# puissance_alim.net
KiCad netlist of a schematic drawn in EAGLE
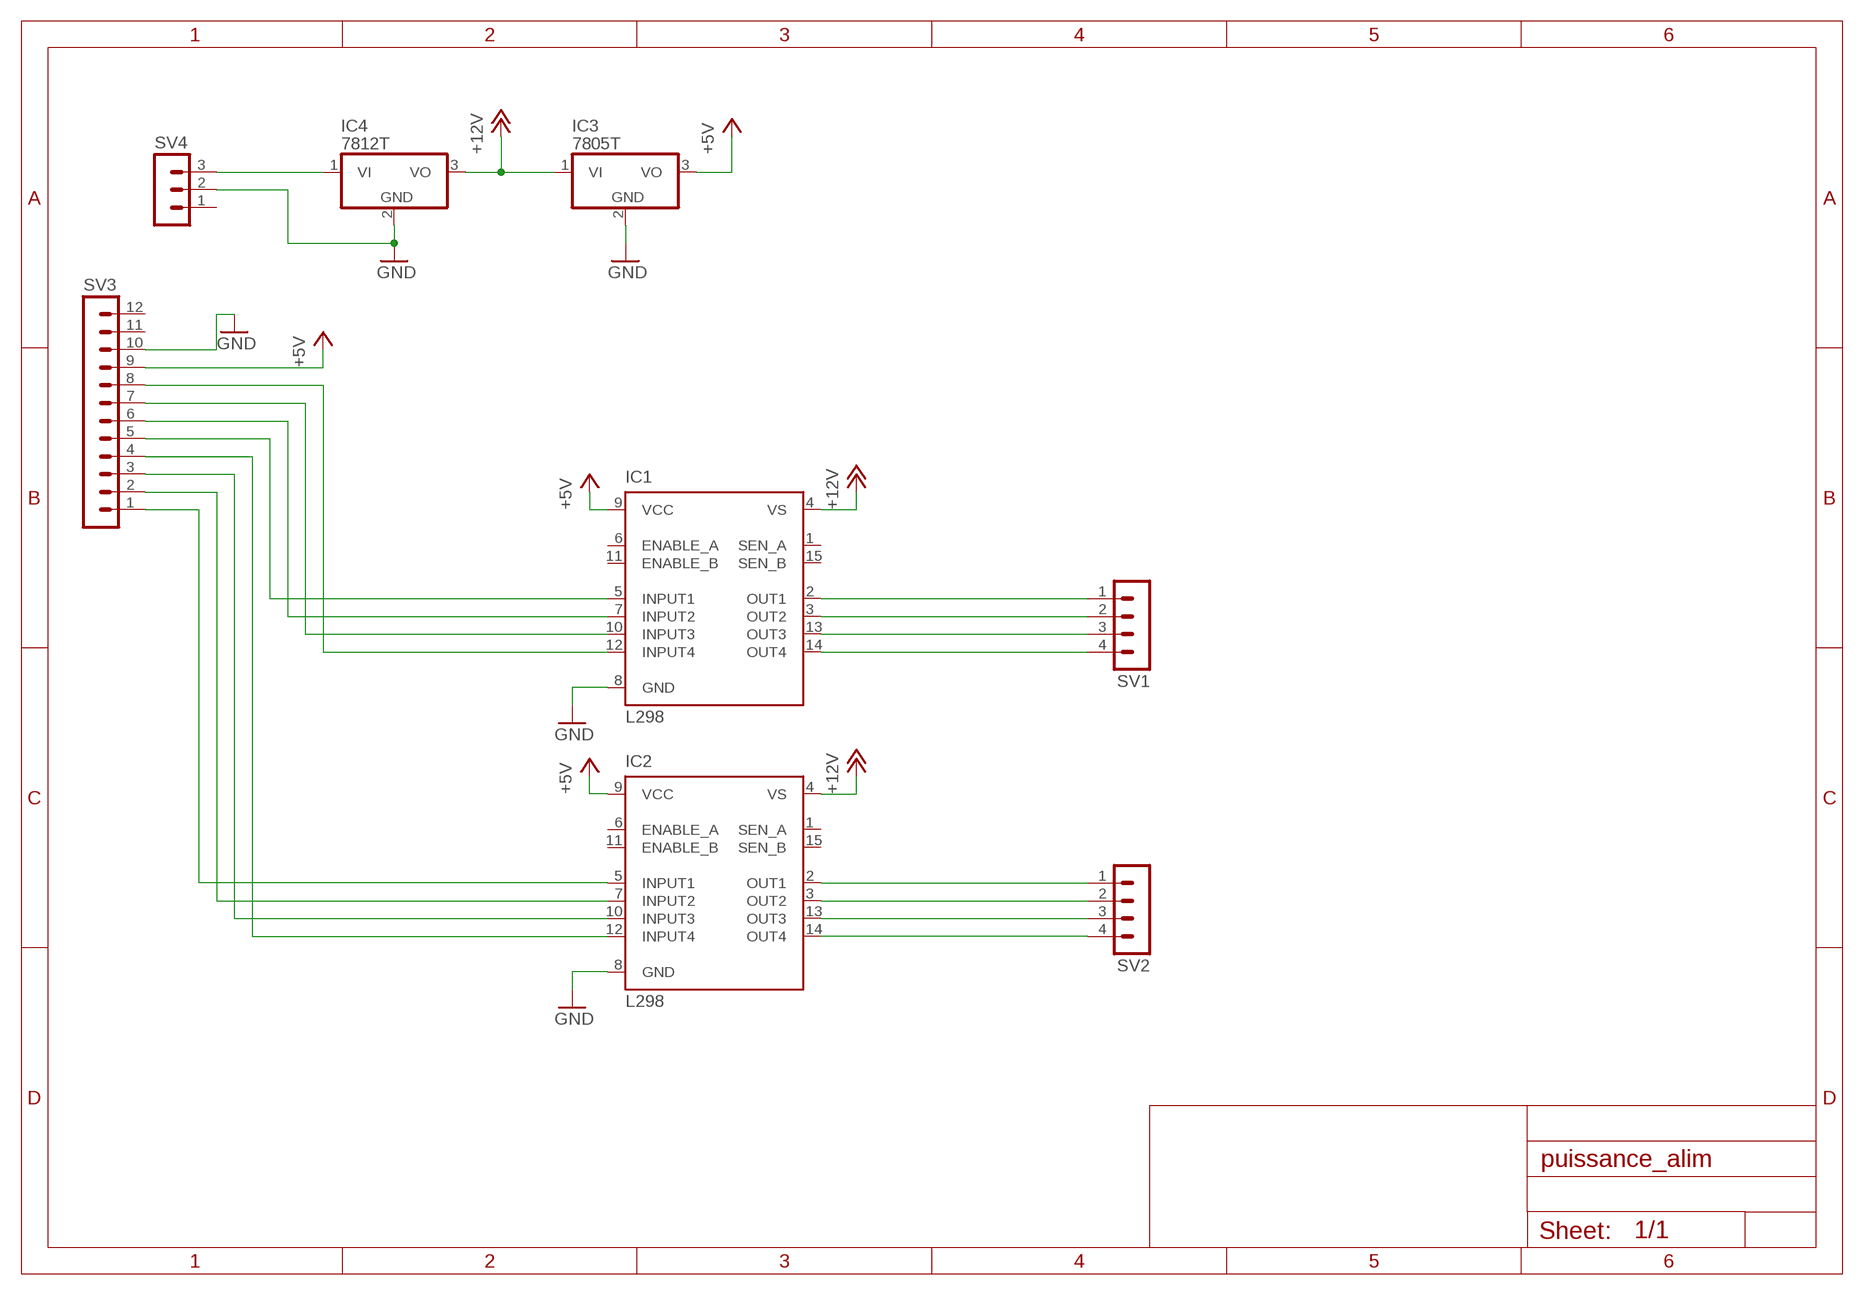
[diagram p0: schematic, sheet 1]

(export (version "E")
  (design (tool "Eeschema 10.0.6"))
  (components
    (comp (ref "IC1")
      (value "L298")
      (footprint "eagle-import:MULTIWATT-15")
      (fields (field (name "MPN") "L298N"))
      (libsource (lib "eagle-import") (part "L298"))
    )
    (comp (ref "IC2")
      (value "L298")
      (footprint "eagle-import:MULTIWATT-15")
      (fields (field (name "MPN") "L298N"))
      (libsource (lib "eagle-import") (part "L298"))
    )
    (comp (ref "IC3")
      (value "7805T")
      (footprint "eagle-import:TO220H")
      (libsource (lib "eagle-import") (part "78T05"))
    )
    (comp (ref "IC4")
      (value "7812T")
      (footprint "eagle-import:TO220H")
      (libsource (lib "eagle-import") (part "78T12"))
    )
    (comp (ref "SV1")
      (value "MA04-1")
      (footprint "eagle-import:MA04-1")
      (libsource (lib "eagle-import") (part "MA04-1"))
    )
    (comp (ref "SV2")
      (value "MA04-1")
      (footprint "eagle-import:MA04-1")
      (libsource (lib "eagle-import") (part "MA04-1"))
    )
    (comp (ref "SV3")
      (value "MA12-1")
      (footprint "eagle-import:MA12-1")
      (libsource (lib "eagle-import") (part "MA12-1"))
    )
    (comp (ref "SV4")
      (value "MA03-1")
      (footprint "eagle-import:MA03-1")
      (libsource (lib "eagle-import") (part "MA03-1"))
    )
  )
  (nets
    (net (code "1") (name "+5V") (class "Default")
      (node (ref "IC1") (pin "9") (pinfunction "VCC_9") (pintype "power_in"))
      (node (ref "IC2") (pin "9") (pinfunction "VCC_9") (pintype "power_in"))
      (node (ref "IC3") (pin "3") (pinfunction "VO_3") (pintype "passive"))
      (node (ref "SV3") (pin "9") (pinfunction "9_9") (pintype "passive"))
    )
    (net (code "2") (name "+12V") (class "Default")
      (node (ref "IC1") (pin "4") (pinfunction "VS_4") (pintype "power_in"))
      (node (ref "IC2") (pin "4") (pinfunction "VS_4") (pintype "power_in"))
      (node (ref "IC3") (pin "1") (pinfunction "VI_1") (pintype "input"))
      (node (ref "IC4") (pin "3") (pinfunction "VO_3") (pintype "passive"))
    )
    (net (code "3") (name "GND") (class "Default")
      (node (ref "IC1") (pin "8") (pinfunction "GND_8") (pintype "power_in"))
      (node (ref "IC2") (pin "8") (pinfunction "GND_8") (pintype "power_in"))
      (node (ref "IC3") (pin "2") (pinfunction "GND_2") (pintype "passive"))
      (node (ref "IC4") (pin "2") (pinfunction "GND_2") (pintype "passive"))
      (node (ref "SV3") (pin "10") (pinfunction "10_10") (pintype "passive"))
      (node (ref "SV4") (pin "2") (pinfunction "2_2") (pintype "passive"))
    )
    (net (code "4") (name "Net-(IC1-INPUT1)") (class "Default")
      (node (ref "IC1") (pin "5") (pinfunction "INPUT1_5") (pintype "input"))
      (node (ref "SV3") (pin "5") (pinfunction "5_5") (pintype "passive"))
    )
    (net (code "5") (name "Net-(IC1-INPUT2)") (class "Default")
      (node (ref "IC1") (pin "7") (pinfunction "INPUT2_7") (pintype "input"))
      (node (ref "SV3") (pin "6") (pinfunction "6_6") (pintype "passive"))
    )
    (net (code "6") (name "Net-(IC1-INPUT3)") (class "Default")
      (node (ref "IC1") (pin "10") (pinfunction "INPUT3_10") (pintype "input"))
      (node (ref "SV3") (pin "7") (pinfunction "7_7") (pintype "passive"))
    )
    (net (code "7") (name "Net-(IC1-INPUT4)") (class "Default")
      (node (ref "IC1") (pin "12") (pinfunction "INPUT4_12") (pintype "input"))
      (node (ref "SV3") (pin "8") (pinfunction "8_8") (pintype "passive"))
    )
    (net (code "8") (name "Net-(IC1-OUT1)") (class "Default")
      (node (ref "IC1") (pin "2") (pinfunction "OUT1_2") (pintype "output"))
      (node (ref "SV1") (pin "1") (pinfunction "1_1") (pintype "passive"))
    )
    (net (code "9") (name "Net-(IC1-OUT2)") (class "Default")
      (node (ref "IC1") (pin "3") (pinfunction "OUT2_3") (pintype "output"))
      (node (ref "SV1") (pin "2") (pinfunction "2_2") (pintype "passive"))
    )
    (net (code "10") (name "Net-(IC1-OUT3)") (class "Default")
      (node (ref "IC1") (pin "13") (pinfunction "OUT3_13") (pintype "output"))
      (node (ref "SV1") (pin "3") (pinfunction "3_3") (pintype "passive"))
    )
    (net (code "11") (name "Net-(IC1-OUT4)") (class "Default")
      (node (ref "IC1") (pin "14") (pinfunction "OUT4_14") (pintype "output"))
      (node (ref "SV1") (pin "4") (pinfunction "4_4") (pintype "passive"))
    )
    (net (code "12") (name "Net-(IC2-INPUT1)") (class "Default")
      (node (ref "IC2") (pin "5") (pinfunction "INPUT1_5") (pintype "input"))
      (node (ref "SV3") (pin "1") (pinfunction "1_1") (pintype "passive"))
    )
    (net (code "13") (name "Net-(IC2-INPUT2)") (class "Default")
      (node (ref "IC2") (pin "7") (pinfunction "INPUT2_7") (pintype "input"))
      (node (ref "SV3") (pin "2") (pinfunction "2_2") (pintype "passive"))
    )
    (net (code "14") (name "Net-(IC2-INPUT3)") (class "Default")
      (node (ref "IC2") (pin "10") (pinfunction "INPUT3_10") (pintype "input"))
      (node (ref "SV3") (pin "3") (pinfunction "3_3") (pintype "passive"))
    )
    (net (code "15") (name "Net-(IC2-INPUT4)") (class "Default")
      (node (ref "IC2") (pin "12") (pinfunction "INPUT4_12") (pintype "input"))
      (node (ref "SV3") (pin "4") (pinfunction "4_4") (pintype "passive"))
    )
    (net (code "16") (name "Net-(IC2-OUT1)") (class "Default")
      (node (ref "IC2") (pin "2") (pinfunction "OUT1_2") (pintype "output"))
      (node (ref "SV2") (pin "1") (pinfunction "1_1") (pintype "passive"))
    )
    (net (code "17") (name "Net-(IC2-OUT2)") (class "Default")
      (node (ref "IC2") (pin "3") (pinfunction "OUT2_3") (pintype "output"))
      (node (ref "SV2") (pin "2") (pinfunction "2_2") (pintype "passive"))
    )
    (net (code "18") (name "Net-(IC2-OUT3)") (class "Default")
      (node (ref "IC2") (pin "13") (pinfunction "OUT3_13") (pintype "output"))
      (node (ref "SV2") (pin "3") (pinfunction "3_3") (pintype "passive"))
    )
    (net (code "19") (name "Net-(IC2-OUT4)") (class "Default")
      (node (ref "IC2") (pin "14") (pinfunction "OUT4_14") (pintype "output"))
      (node (ref "SV2") (pin "4") (pinfunction "4_4") (pintype "passive"))
    )
    (net (code "20") (name "Net-(IC4-VI)") (class "Default")
      (node (ref "IC4") (pin "1") (pinfunction "VI_1") (pintype "input"))
      (node (ref "SV4") (pin "3") (pinfunction "3_3") (pintype "passive"))
    )
    (net (code "21") (name "unconnected-(IC1-ENABLE_A-Pad6)") (class "Default")
      (node (ref "IC1") (pin "6") (pinfunction "ENABLE_A_6") (pintype "input"))
    )
    (net (code "22") (name "unconnected-(IC1-ENABLE_B-Pad11)") (class "Default")
      (node (ref "IC1") (pin "11") (pinfunction "ENABLE_B_11") (pintype "input"))
    )
    (net (code "23") (name "unconnected-(IC1-SEN_A-Pad1)") (class "Default")
      (node (ref "IC1") (pin "1") (pinfunction "SEN_A_1") (pintype "input"))
    )
    (net (code "24") (name "unconnected-(IC1-SEN_B-Pad15)") (class "Default")
      (node (ref "IC1") (pin "15") (pinfunction "SEN_B_15") (pintype "input"))
    )
    (net (code "25") (name "unconnected-(IC2-ENABLE_A-Pad6)") (class "Default")
      (node (ref "IC2") (pin "6") (pinfunction "ENABLE_A_6") (pintype "input"))
    )
    (net (code "26") (name "unconnected-(IC2-ENABLE_B-Pad11)") (class "Default")
      (node (ref "IC2") (pin "11") (pinfunction "ENABLE_B_11") (pintype "input"))
    )
    (net (code "27") (name "unconnected-(IC2-SEN_A-Pad1)") (class "Default")
      (node (ref "IC2") (pin "1") (pinfunction "SEN_A_1") (pintype "input"))
    )
    (net (code "28") (name "unconnected-(IC2-SEN_B-Pad15)") (class "Default")
      (node (ref "IC2") (pin "15") (pinfunction "SEN_B_15") (pintype "input"))
    )
    (net (code "29") (name "unconnected-(SV3-Pad11)") (class "Default")
      (node (ref "SV3") (pin "11") (pinfunction "11_11") (pintype "passive"))
    )
    (net (code "30") (name "unconnected-(SV3-Pad12)") (class "Default")
      (node (ref "SV3") (pin "12") (pinfunction "12_12") (pintype "passive"))
    )
    (net (code "31") (name "unconnected-(SV4-Pad1)") (class "Default")
      (node (ref "SV4") (pin "1") (pinfunction "1_1") (pintype "passive"))
    )
  )
)
